# MCB-Pine64-IoT-Stamp-v1_0_0.net
KiCad netlist of a schematic drawn in EAGLE
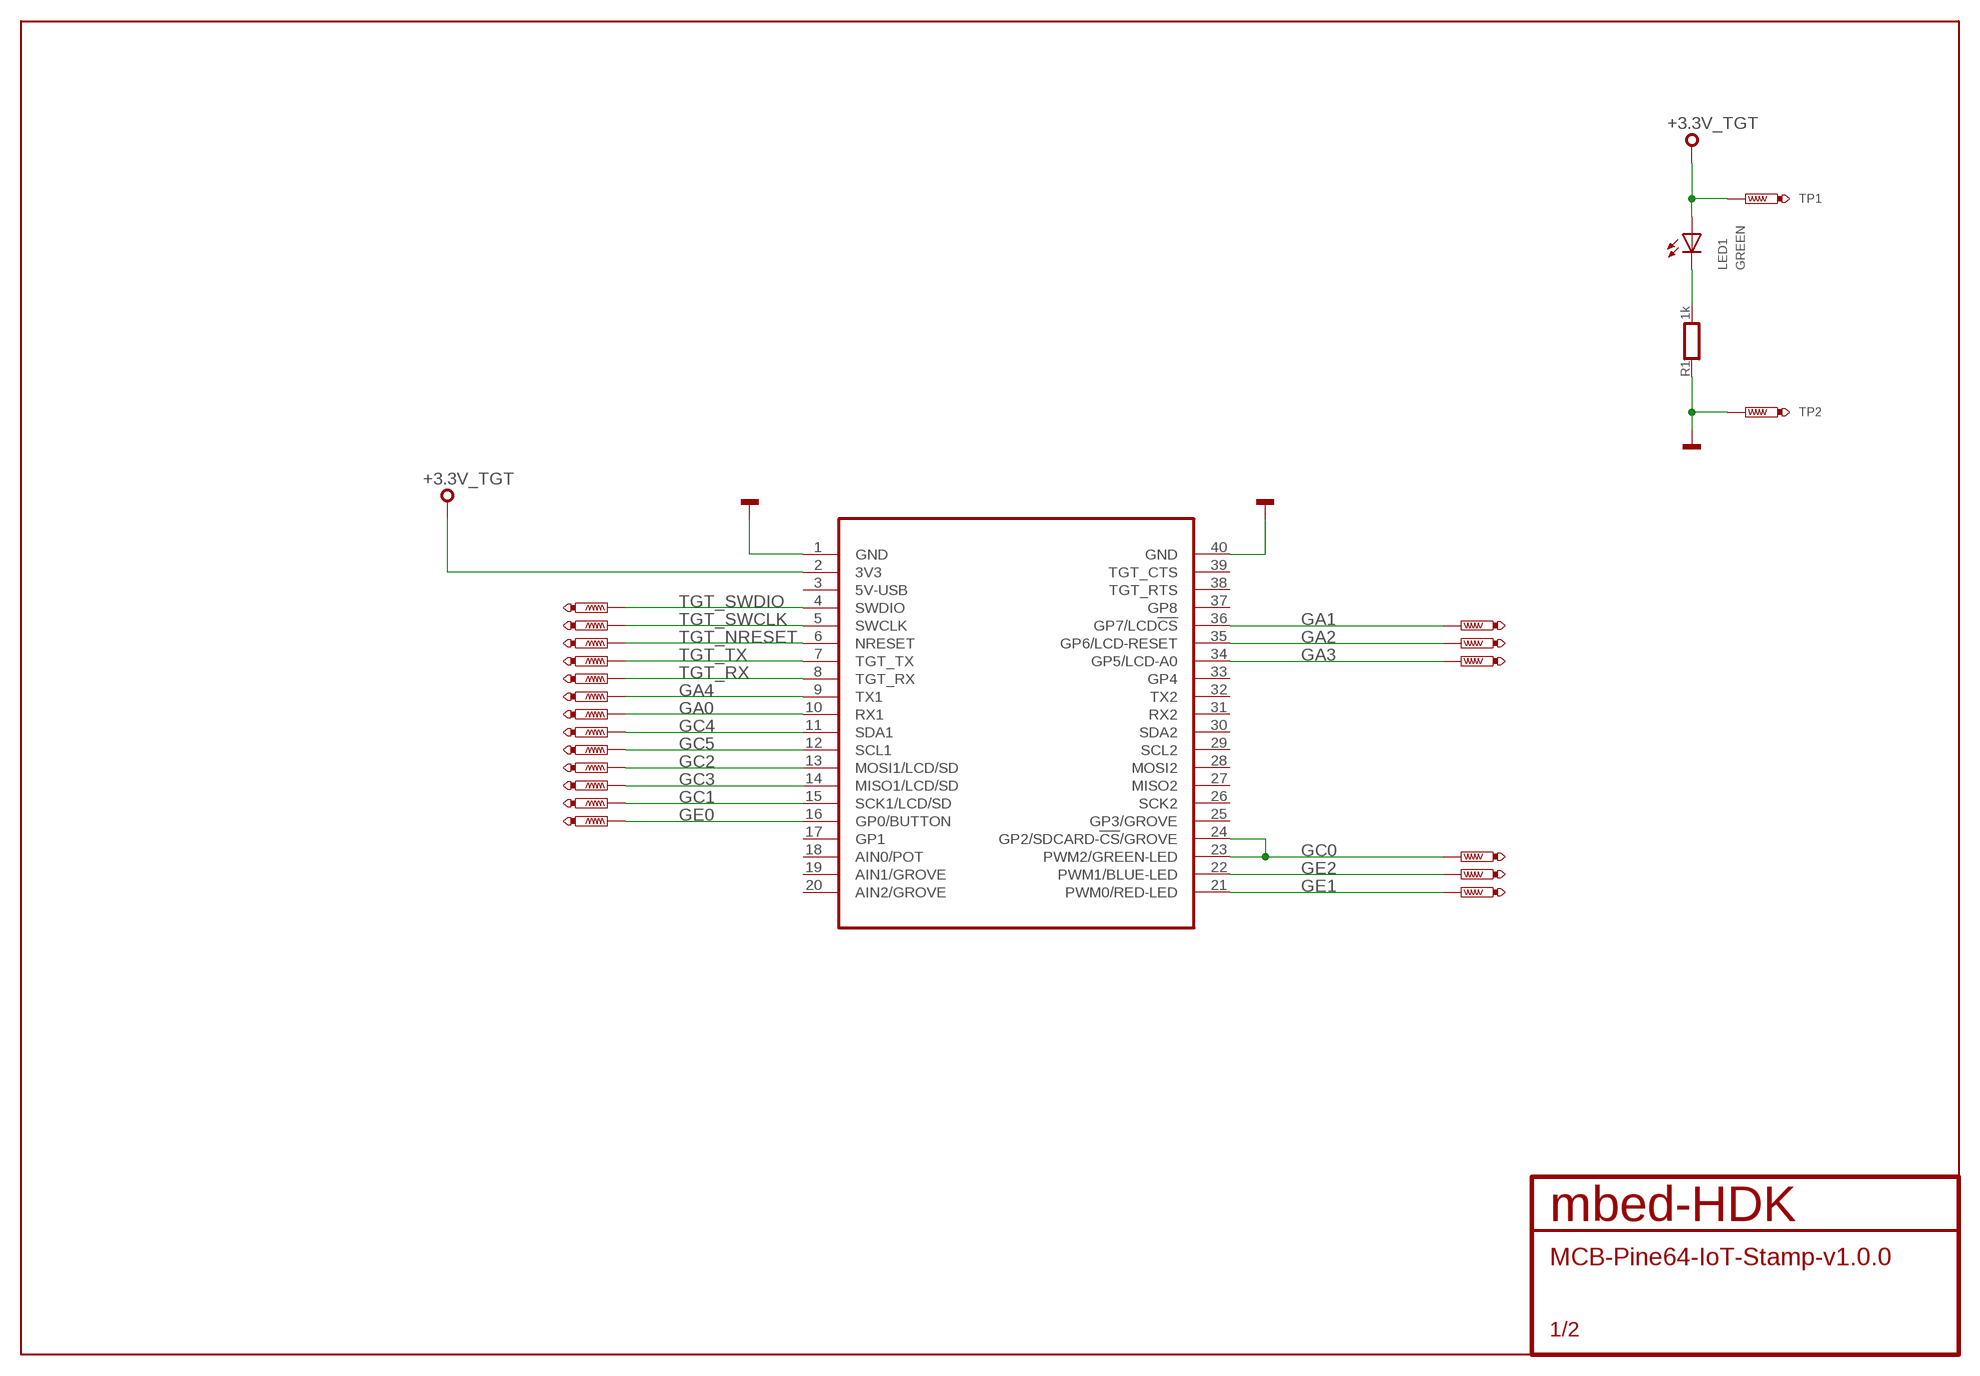
[diagram p0: schematic, sheet 1]
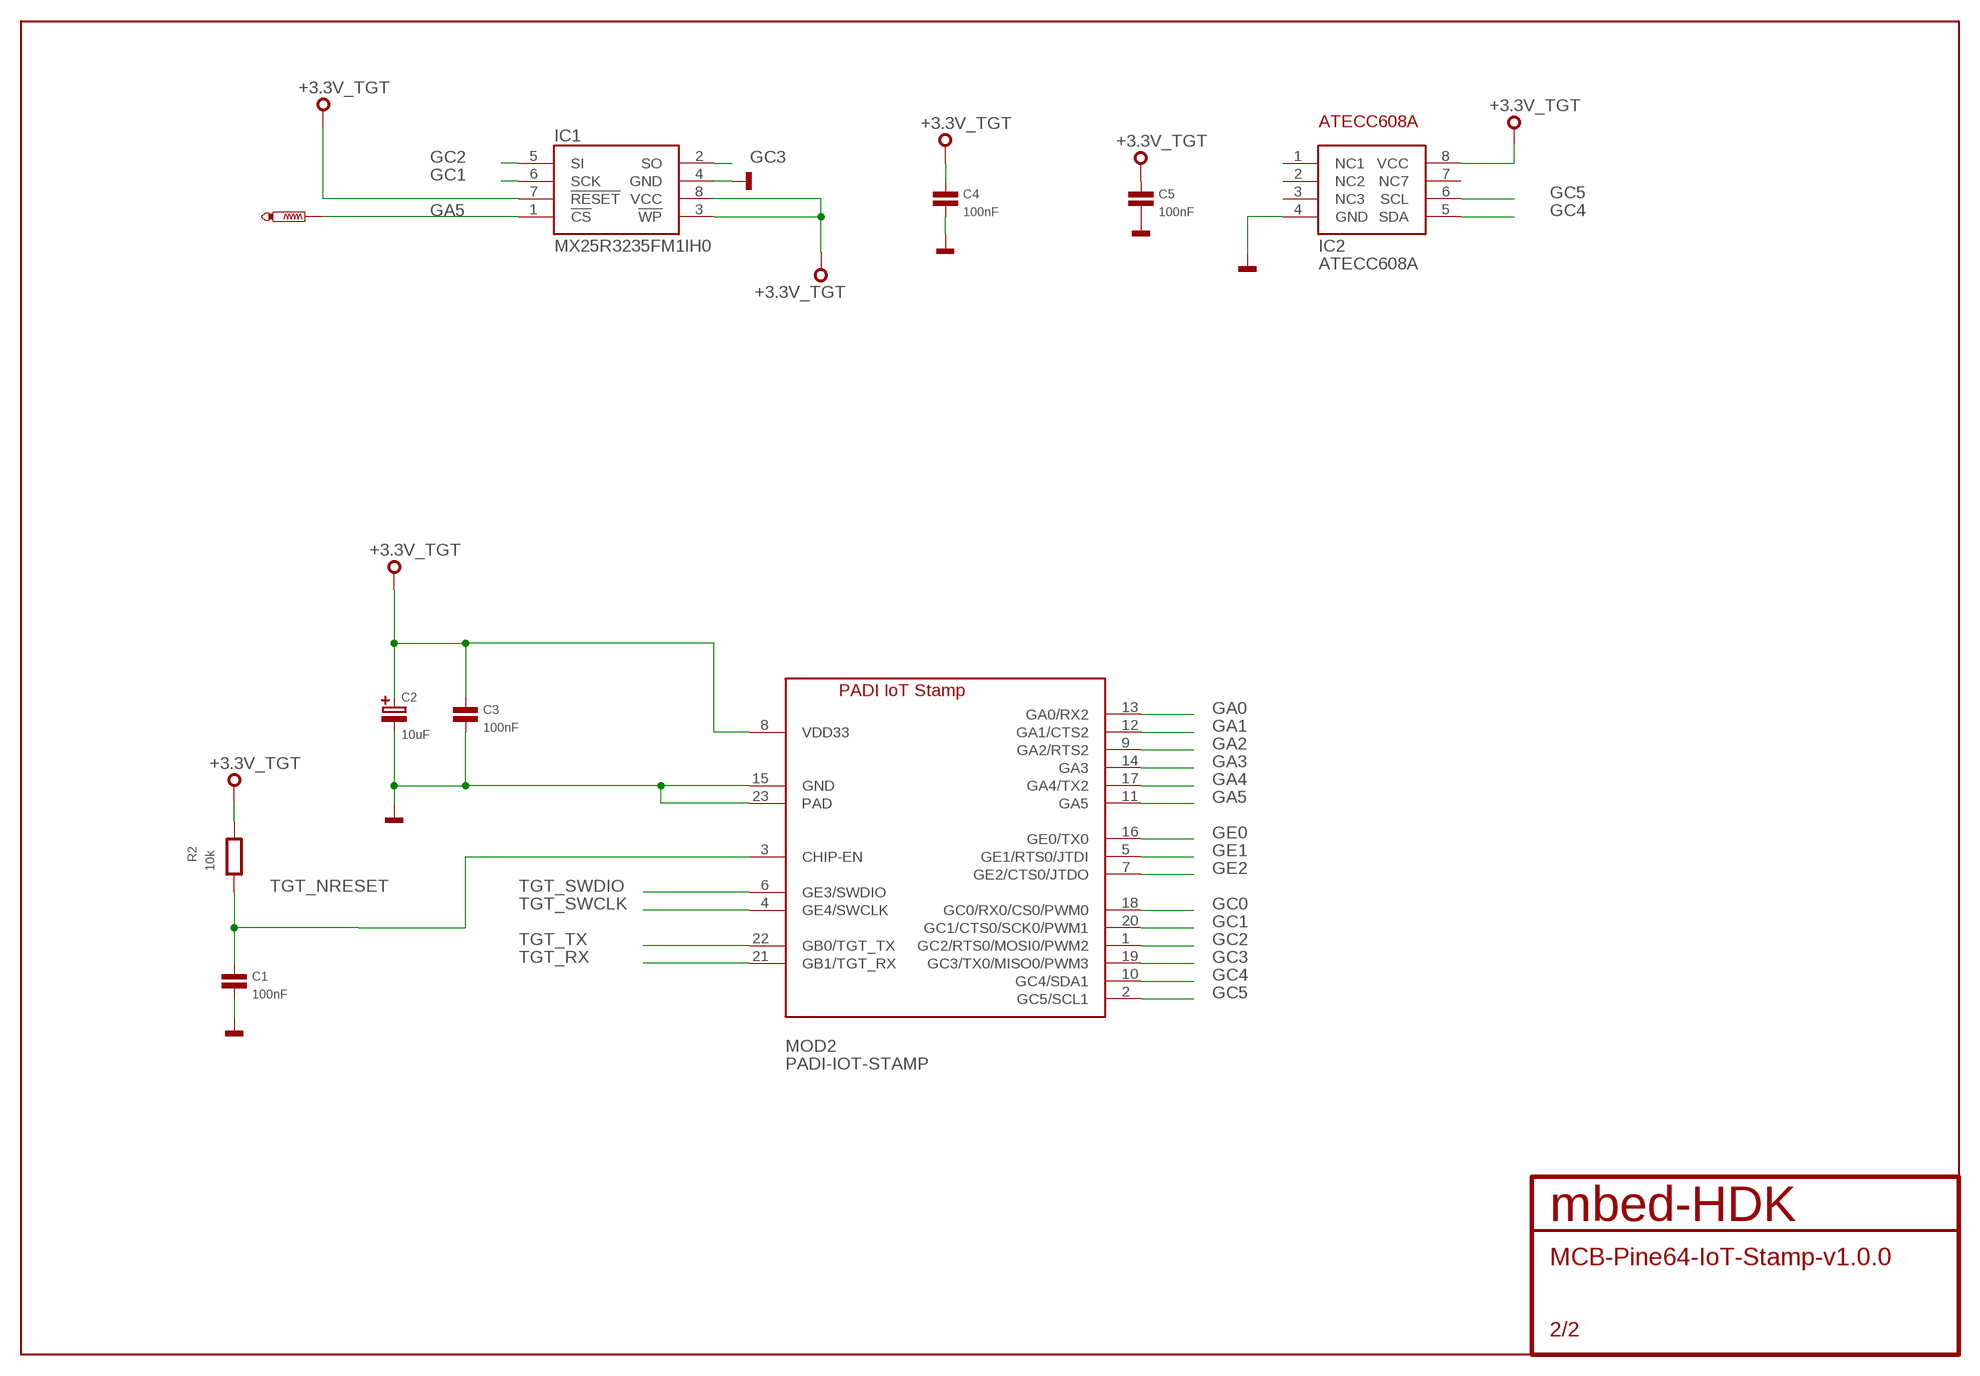
[diagram p1: schematic, sheet 2]

(export (version "E")
  (design (tool "Eeschema 10.0.6"))
  (components
    (comp (ref "C1")
      (value "100nF")
      (footprint "eagle-import:0603")
      (libsource (lib "eagle-import") (part "C0603"))
    )
    (comp (ref "C2")
      (value "10uF")
      (footprint "eagle-import:SMC_B")
      (fields (field (name "MF") "Kemet"))
      (libsource (lib "eagle-import") (part "CAPACITOR-POLARISEDB"))
    )
    (comp (ref "C3")
      (value "100nF")
      (footprint "eagle-import:0603")
      (libsource (lib "eagle-import") (part "C0603"))
    )
    (comp (ref "C4")
      (value "100nF")
      (footprint "eagle-import:0603")
      (libsource (lib "eagle-import") (part "C0603"))
    )
    (comp (ref "C5")
      (value "100nF")
      (footprint "eagle-import:0603")
      (libsource (lib "eagle-import") (part "C0603"))
    )
    (comp (ref "IC1")
      (value "MX25R3235FM1IH0")
      (footprint "eagle-import:SO8")
      (fields (field (name "MF") "Macronix"))
      (libsource (lib "eagle-import") (part "MX25R3235FM1IH0"))
    )
    (comp (ref "IC2")
      (value "ATECC608A")
      (footprint "eagle-import:SO8")
      (fields (field (name "MF") "Atmel"))
      (libsource (lib "eagle-import") (part "ATECC608A"))
    )
    (comp (ref "MOD2")
      (value "PADI-IOT-STAMP")
      (footprint "eagle-import:PADI-IOT-STAMP")
      (libsource (lib "eagle-import") (part "PADI-IOT-STAMP"))
    )
    (comp (ref "R2")
      (value "10k")
      (footprint "eagle-import:0603")
      (libsource (lib "eagle-import") (part "RESISTOR0603"))
    )
    (comp (ref "TP5")
      (value "PTR1TP07R")
      (footprint "eagle-import:TP07R")
      (libsource (lib "eagle-import") (part "PTR1TP07R"))
    )
    (comp (ref "LED1")
      (value "GREEN")
      (footprint "eagle-import:CHIPLED_0603")
      (fields (field (name "MF") "Wurth Electronics Inc"))
      (libsource (lib "eagle-import") (part "SMD_LED0603"))
    )
    (comp (ref "MOD1")
      (value "MODULE_DAUGHTER")
      (footprint "eagle-import:MODULE_DAUGHTER")
      (libsource (lib "eagle-import") (part "MODULE_DAUGHTER"))
    )
    (comp (ref "R1")
      (value "1k")
      (footprint "eagle-import:0603")
      (libsource (lib "eagle-import") (part "RESISTOR0603"))
    )
    (comp (ref "TP1")
      (value "TEST-POINT-50R-PTH")
      (footprint "eagle-import:TP50-PTH")
      (libsource (lib "eagle-import") (part "TEST-POINT-50R-PTH"))
    )
    (comp (ref "TP2")
      (value "TEST-POINT-50R-PTH")
      (footprint "eagle-import:TP50-PTH")
      (libsource (lib "eagle-import") (part "TEST-POINT-50R-PTH"))
    )
    (comp (ref "TP3")
      (value "PTR1TP07R")
      (footprint "eagle-import:TP07R")
      (libsource (lib "eagle-import") (part "PTR1TP07R"))
    )
    (comp (ref "TP4")
      (value "PTR1TP07R")
      (footprint "eagle-import:TP07R")
      (libsource (lib "eagle-import") (part "PTR1TP07R"))
    )
    (comp (ref "TP7")
      (value "PTR1TP07R")
      (footprint "eagle-import:TP07R")
      (libsource (lib "eagle-import") (part "PTR1TP07R"))
    )
    (comp (ref "TP8")
      (value "PTR1TP07R")
      (footprint "eagle-import:TP07R")
      (libsource (lib "eagle-import") (part "PTR1TP07R"))
    )
    (comp (ref "TP9")
      (value "PTR1TP07R")
      (footprint "eagle-import:TP07R")
      (libsource (lib "eagle-import") (part "PTR1TP07R"))
    )
    (comp (ref "TP13")
      (value "PTR1TP07R")
      (footprint "eagle-import:TP07R")
      (libsource (lib "eagle-import") (part "PTR1TP07R"))
    )
    (comp (ref "TP14")
      (value "PTR1TP07R")
      (footprint "eagle-import:TP07R")
      (libsource (lib "eagle-import") (part "PTR1TP07R"))
    )
    (comp (ref "TP15")
      (value "PTR1TP07R")
      (footprint "eagle-import:TP07R")
      (libsource (lib "eagle-import") (part "PTR1TP07R"))
    )
    (comp (ref "TP17")
      (value "PTR1TP07R")
      (footprint "eagle-import:TP07R")
      (libsource (lib "eagle-import") (part "PTR1TP07R"))
    )
    (comp (ref "TP19")
      (value "PTR1TP07R")
      (footprint "eagle-import:TP07R")
      (libsource (lib "eagle-import") (part "PTR1TP07R"))
    )
    (comp (ref "TP20")
      (value "PTR1TP07R")
      (footprint "eagle-import:TP07R")
      (libsource (lib "eagle-import") (part "PTR1TP07R"))
    )
    (comp (ref "TP21")
      (value "PTR1TP07R")
      (footprint "eagle-import:TP07R")
      (libsource (lib "eagle-import") (part "PTR1TP07R"))
    )
    (comp (ref "TP22")
      (value "PTR1TP07R")
      (footprint "eagle-import:TP07R")
      (libsource (lib "eagle-import") (part "PTR1TP07R"))
    )
    (comp (ref "TP25")
      (value "PTR1TP07R")
      (footprint "eagle-import:TP07R")
      (libsource (lib "eagle-import") (part "PTR1TP07R"))
    )
    (comp (ref "TP26")
      (value "PTR1TP07R")
      (footprint "eagle-import:TP07R")
      (libsource (lib "eagle-import") (part "PTR1TP07R"))
    )
    (comp (ref "TP27")
      (value "PTR1TP07R")
      (footprint "eagle-import:TP07R")
      (libsource (lib "eagle-import") (part "PTR1TP07R"))
    )
    (comp (ref "TP28")
      (value "PTR1TP07R")
      (footprint "eagle-import:TP07R")
      (libsource (lib "eagle-import") (part "PTR1TP07R"))
    )
    (comp (ref "TP29")
      (value "PTR1TP07R")
      (footprint "eagle-import:TP07R")
      (libsource (lib "eagle-import") (part "PTR1TP07R"))
    )
    (comp (ref "TP30")
      (value "PTR1TP07R")
      (footprint "eagle-import:TP07R")
      (libsource (lib "eagle-import") (part "PTR1TP07R"))
    )
  )
  (nets
    (net (code "1") (name "+3.3V_TGT") (class "Default")
      (node (ref "C2") (pin "+") (pinfunction "+_+") (pintype "passive"))
      (node (ref "C3") (pin "1") (pinfunction "P$1_1") (pintype "passive"))
      (node (ref "C4") (pin "1") (pinfunction "P$1_1") (pintype "passive"))
      (node (ref "C5") (pin "1") (pinfunction "P$1_1") (pintype "passive"))
      (node (ref "IC1") (pin "3") (pinfunction "~{WP}_3") (pintype "bidirectional"))
      (node (ref "IC1") (pin "7") (pinfunction "~{RESET}_7") (pintype "bidirectional"))
      (node (ref "IC1") (pin "8") (pinfunction "VCC_8") (pintype "bidirectional"))
      (node (ref "IC2") (pin "8") (pinfunction "VCC_8") (pintype "bidirectional"))
      (node (ref "LED1") (pin "A") (pinfunction "A_A") (pintype "passive"))
      (node (ref "MOD1") (pin "2") (pinfunction "3V3_2") (pintype "bidirectional"))
      (node (ref "MOD2") (pin "8") (pinfunction "VDD33_8") (pintype "bidirectional"))
      (node (ref "R2") (pin "2") (pinfunction "P$2_2") (pintype "passive"))
      (node (ref "TP1") (pin "TP") (pinfunction "TP_TP") (pintype "input"))
    )
    (net (code "2") (name "GA0") (class "Default")
      (node (ref "MOD1") (pin "10") (pinfunction "RX1_10") (pintype "bidirectional"))
      (node (ref "MOD2") (pin "13") (pinfunction "GA0/RX2_13") (pintype "bidirectional"))
      (node (ref "TP21") (pin "TP") (pinfunction "TP_TP") (pintype "input"))
    )
    (net (code "3") (name "GA1") (class "Default")
      (node (ref "MOD1") (pin "36") (pinfunction "GP7/LCD~{CS}_36") (pintype "bidirectional"))
      (node (ref "MOD2") (pin "12") (pinfunction "GA1/CTS2_12") (pintype "bidirectional"))
      (node (ref "TP25") (pin "TP") (pinfunction "TP_TP") (pintype "input"))
    )
    (net (code "4") (name "GA2") (class "Default")
      (node (ref "MOD1") (pin "35") (pinfunction "GP6/LCD-RESET_35") (pintype "bidirectional"))
      (node (ref "MOD2") (pin "9") (pinfunction "GA2/RTS2_9") (pintype "bidirectional"))
      (node (ref "TP20") (pin "TP") (pinfunction "TP_TP") (pintype "input"))
    )
    (net (code "5") (name "GA3") (class "Default")
      (node (ref "MOD1") (pin "34") (pinfunction "GP5/LCD-A0_34") (pintype "bidirectional"))
      (node (ref "MOD2") (pin "14") (pinfunction "GA3_14") (pintype "bidirectional"))
      (node (ref "TP19") (pin "TP") (pinfunction "TP_TP") (pintype "input"))
    )
    (net (code "6") (name "GA4") (class "Default")
      (node (ref "MOD1") (pin "9") (pinfunction "TX1_9") (pintype "bidirectional"))
      (node (ref "MOD2") (pin "17") (pinfunction "GA4/TX2_17") (pintype "bidirectional"))
      (node (ref "TP22") (pin "TP") (pinfunction "TP_TP") (pintype "input"))
    )
    (net (code "7") (name "GA5") (class "Default")
      (node (ref "IC1") (pin "1") (pinfunction "~{CS}_1") (pintype "bidirectional"))
      (node (ref "MOD2") (pin "11") (pinfunction "GA5_11") (pintype "bidirectional"))
      (node (ref "TP5") (pin "TP") (pinfunction "TP_TP") (pintype "input"))
    )
    (net (code "8") (name "GC0") (class "Default")
      (node (ref "MOD1") (pin "23") (pinfunction "PWM2/GREEN-LED_23") (pintype "bidirectional"))
      (node (ref "MOD1") (pin "24") (pinfunction "GP2/SDCARD-~{CS}/GROVE_24") (pintype "bidirectional"))
      (node (ref "MOD2") (pin "18") (pinfunction "GC0/RX0/CS0/PWM0_18") (pintype "bidirectional"))
      (node (ref "TP15") (pin "TP") (pinfunction "TP_TP") (pintype "input"))
    )
    (net (code "9") (name "GC1") (class "Default")
      (node (ref "IC1") (pin "6") (pinfunction "SCK_6") (pintype "bidirectional"))
      (node (ref "MOD1") (pin "15") (pinfunction "SCK1/LCD/SD_15") (pintype "bidirectional"))
      (node (ref "MOD2") (pin "20") (pinfunction "GC1/CTS0/SCK0/PWM1_20") (pintype "bidirectional"))
      (node (ref "TP9") (pin "TP") (pinfunction "TP_TP") (pintype "input"))
    )
    (net (code "10") (name "GC2") (class "Default")
      (node (ref "IC1") (pin "5") (pinfunction "SI_5") (pintype "bidirectional"))
      (node (ref "MOD1") (pin "13") (pinfunction "MOSI1/LCD/SD_13") (pintype "bidirectional"))
      (node (ref "MOD2") (pin "1") (pinfunction "GC2/RTS0/MOSI0/PWM2_1") (pintype "bidirectional"))
      (node (ref "TP7") (pin "TP") (pinfunction "TP_TP") (pintype "input"))
    )
    (net (code "11") (name "GC3") (class "Default")
      (node (ref "IC1") (pin "2") (pinfunction "SO_2") (pintype "bidirectional"))
      (node (ref "MOD1") (pin "14") (pinfunction "MISO1/LCD/SD_14") (pintype "bidirectional"))
      (node (ref "MOD2") (pin "19") (pinfunction "GC3/TX0/MISO0/PWM3_19") (pintype "bidirectional"))
      (node (ref "TP8") (pin "TP") (pinfunction "TP_TP") (pintype "input"))
    )
    (net (code "12") (name "GC4") (class "Default")
      (node (ref "IC2") (pin "5") (pinfunction "SDA_5") (pintype "bidirectional"))
      (node (ref "MOD1") (pin "11") (pinfunction "SDA1_11") (pintype "bidirectional"))
      (node (ref "MOD2") (pin "10") (pinfunction "GC4/SDA1_10") (pintype "bidirectional"))
      (node (ref "TP3") (pin "TP") (pinfunction "TP_TP") (pintype "input"))
    )
    (net (code "13") (name "GC5") (class "Default")
      (node (ref "IC2") (pin "6") (pinfunction "SCL_6") (pintype "bidirectional"))
      (node (ref "MOD1") (pin "12") (pinfunction "SCL1_12") (pintype "bidirectional"))
      (node (ref "MOD2") (pin "2") (pinfunction "GC5/SCL1_2") (pintype "bidirectional"))
      (node (ref "TP4") (pin "TP") (pinfunction "TP_TP") (pintype "input"))
    )
    (net (code "14") (name "GE0") (class "Default")
      (node (ref "MOD1") (pin "16") (pinfunction "GP0/BUTTON_16") (pintype "bidirectional"))
      (node (ref "MOD2") (pin "16") (pinfunction "GE0/TX0_16") (pintype "bidirectional"))
      (node (ref "TP17") (pin "TP") (pinfunction "TP_TP") (pintype "input"))
    )
    (net (code "15") (name "GE1") (class "Default")
      (node (ref "MOD1") (pin "21") (pinfunction "PWM0/RED-LED_21") (pintype "bidirectional"))
      (node (ref "MOD2") (pin "5") (pinfunction "GE1/RTS0/JTDI_5") (pintype "bidirectional"))
      (node (ref "TP13") (pin "TP") (pinfunction "TP_TP") (pintype "input"))
    )
    (net (code "16") (name "GE2") (class "Default")
      (node (ref "MOD1") (pin "22") (pinfunction "PWM1/BLUE-LED_22") (pintype "bidirectional"))
      (node (ref "MOD2") (pin "7") (pinfunction "GE2/CTS0/JTDO_7") (pintype "bidirectional"))
      (node (ref "TP14") (pin "TP") (pinfunction "TP_TP") (pintype "input"))
    )
    (net (code "17") (name "GND") (class "Default")
      (node (ref "C1") (pin "2") (pinfunction "P$2_2") (pintype "passive"))
      (node (ref "C2") (pin "-") (pinfunction "-_-") (pintype "passive"))
      (node (ref "C3") (pin "2") (pinfunction "P$2_2") (pintype "passive"))
      (node (ref "C4") (pin "2") (pinfunction "P$2_2") (pintype "passive"))
      (node (ref "C5") (pin "2") (pinfunction "P$2_2") (pintype "passive"))
      (node (ref "IC1") (pin "4") (pinfunction "GND_4") (pintype "bidirectional"))
      (node (ref "IC2") (pin "4") (pinfunction "GND_4") (pintype "bidirectional"))
      (node (ref "MOD1") (pin "1") (pinfunction "GND_1") (pintype "bidirectional"))
      (node (ref "MOD1") (pin "40") (pinfunction "GND_40") (pintype "bidirectional"))
      (node (ref "MOD2") (pin "15") (pinfunction "GND_15") (pintype "bidirectional"))
      (node (ref "MOD2") (pin "23") (pinfunction "PAD_23") (pintype "bidirectional"))
      (node (ref "R1") (pin "1") (pinfunction "P$1_1") (pintype "passive"))
      (node (ref "TP2") (pin "TP") (pinfunction "TP_TP") (pintype "input"))
    )
    (net (code "18") (name "Net-(R1-P$2)") (class "Default")
      (node (ref "LED1") (pin "C") (pinfunction "C_C") (pintype "passive"))
      (node (ref "R1") (pin "2") (pinfunction "P$2_2") (pintype "passive"))
    )
    (net (code "19") (name "TGT_NRESET") (class "Default")
      (node (ref "C1") (pin "1") (pinfunction "P$1_1") (pintype "passive"))
      (node (ref "MOD1") (pin "6") (pinfunction "NRESET_6") (pintype "bidirectional"))
      (node (ref "MOD2") (pin "3") (pinfunction "CHIP-EN_3") (pintype "bidirectional"))
      (node (ref "R2") (pin "1") (pinfunction "P$1_1") (pintype "passive"))
      (node (ref "TP28") (pin "TP") (pinfunction "TP_TP") (pintype "input"))
    )
    (net (code "20") (name "TGT_RX") (class "Default")
      (node (ref "MOD1") (pin "8") (pinfunction "TGT_RX_8") (pintype "bidirectional"))
      (node (ref "MOD2") (pin "21") (pinfunction "GB1/TGT_RX_21") (pintype "bidirectional"))
      (node (ref "TP30") (pin "TP") (pinfunction "TP_TP") (pintype "input"))
    )
    (net (code "21") (name "TGT_SWCLK") (class "Default")
      (node (ref "MOD1") (pin "5") (pinfunction "SWCLK_5") (pintype "bidirectional"))
      (node (ref "MOD2") (pin "4") (pinfunction "GE4/SWCLK_4") (pintype "bidirectional"))
      (node (ref "TP27") (pin "TP") (pinfunction "TP_TP") (pintype "input"))
    )
    (net (code "22") (name "TGT_SWDIO") (class "Default")
      (node (ref "MOD1") (pin "4") (pinfunction "SWDIO_4") (pintype "bidirectional"))
      (node (ref "MOD2") (pin "6") (pinfunction "GE3/SWDIO_6") (pintype "bidirectional"))
      (node (ref "TP26") (pin "TP") (pinfunction "TP_TP") (pintype "input"))
    )
    (net (code "23") (name "TGT_TX") (class "Default")
      (node (ref "MOD1") (pin "7") (pinfunction "TGT_TX_7") (pintype "bidirectional"))
      (node (ref "MOD2") (pin "22") (pinfunction "GB0/TGT_TX_22") (pintype "bidirectional"))
      (node (ref "TP29") (pin "TP") (pinfunction "TP_TP") (pintype "input"))
    )
    (net (code "24") (name "unconnected-(IC2-NC1-Pad1)") (class "Default")
      (node (ref "IC2") (pin "1") (pinfunction "NC1_1") (pintype "bidirectional"))
    )
    (net (code "25") (name "unconnected-(IC2-NC2-Pad2)") (class "Default")
      (node (ref "IC2") (pin "2") (pinfunction "NC2_2") (pintype "bidirectional"))
    )
    (net (code "26") (name "unconnected-(IC2-NC3-Pad3)") (class "Default")
      (node (ref "IC2") (pin "3") (pinfunction "NC3_3") (pintype "bidirectional"))
    )
    (net (code "27") (name "unconnected-(IC2-NC7-Pad7)") (class "Default")
      (node (ref "IC2") (pin "7") (pinfunction "NC7_7") (pintype "bidirectional"))
    )
    (net (code "28") (name "unconnected-(MOD1-5V-USB-Pad3)") (class "Default")
      (node (ref "MOD1") (pin "3") (pinfunction "5V-USB_3") (pintype "bidirectional"))
    )
    (net (code "29") (name "unconnected-(MOD1-AIN0{slash}POT-Pad18)") (class "Default")
      (node (ref "MOD1") (pin "18") (pinfunction "AIN0/POT_18") (pintype "bidirectional"))
    )
    (net (code "30") (name "unconnected-(MOD1-AIN1{slash}GROVE-Pad19)") (class "Default")
      (node (ref "MOD1") (pin "19") (pinfunction "AIN1/GROVE_19") (pintype "bidirectional"))
    )
    (net (code "31") (name "unconnected-(MOD1-AIN2{slash}GROVE-Pad20)") (class "Default")
      (node (ref "MOD1") (pin "20") (pinfunction "AIN2/GROVE_20") (pintype "bidirectional"))
    )
    (net (code "32") (name "unconnected-(MOD1-GP1-Pad17)") (class "Default")
      (node (ref "MOD1") (pin "17") (pinfunction "GP1_17") (pintype "bidirectional"))
    )
    (net (code "33") (name "unconnected-(MOD1-GP3{slash}GROVE-Pad25)") (class "Default")
      (node (ref "MOD1") (pin "25") (pinfunction "GP3/GROVE_25") (pintype "bidirectional"))
    )
    (net (code "34") (name "unconnected-(MOD1-GP4-Pad33)") (class "Default")
      (node (ref "MOD1") (pin "33") (pinfunction "GP4_33") (pintype "bidirectional"))
    )
    (net (code "35") (name "unconnected-(MOD1-GP8-Pad37)") (class "Default")
      (node (ref "MOD1") (pin "37") (pinfunction "GP8_37") (pintype "bidirectional"))
    )
    (net (code "36") (name "unconnected-(MOD1-MISO2-Pad27)") (class "Default")
      (node (ref "MOD1") (pin "27") (pinfunction "MISO2_27") (pintype "bidirectional"))
    )
    (net (code "37") (name "unconnected-(MOD1-MOSI2-Pad28)") (class "Default")
      (node (ref "MOD1") (pin "28") (pinfunction "MOSI2_28") (pintype "bidirectional"))
    )
    (net (code "38") (name "unconnected-(MOD1-RX2-Pad31)") (class "Default")
      (node (ref "MOD1") (pin "31") (pinfunction "RX2_31") (pintype "bidirectional"))
    )
    (net (code "39") (name "unconnected-(MOD1-SCK2-Pad26)") (class "Default")
      (node (ref "MOD1") (pin "26") (pinfunction "SCK2_26") (pintype "bidirectional"))
    )
    (net (code "40") (name "unconnected-(MOD1-SCL2-Pad29)") (class "Default")
      (node (ref "MOD1") (pin "29") (pinfunction "SCL2_29") (pintype "bidirectional"))
    )
    (net (code "41") (name "unconnected-(MOD1-SDA2-Pad30)") (class "Default")
      (node (ref "MOD1") (pin "30") (pinfunction "SDA2_30") (pintype "bidirectional"))
    )
    (net (code "42") (name "unconnected-(MOD1-TGT_CTS-Pad39)") (class "Default")
      (node (ref "MOD1") (pin "39") (pinfunction "TGT_CTS_39") (pintype "bidirectional"))
    )
    (net (code "43") (name "unconnected-(MOD1-TGT_RTS-Pad38)") (class "Default")
      (node (ref "MOD1") (pin "38") (pinfunction "TGT_RTS_38") (pintype "bidirectional"))
    )
    (net (code "44") (name "unconnected-(MOD1-TX2-Pad32)") (class "Default")
      (node (ref "MOD1") (pin "32") (pinfunction "TX2_32") (pintype "bidirectional"))
    )
  )
)
